# Power.net
KiCad netlist of a schematic drawn in Altium Designer
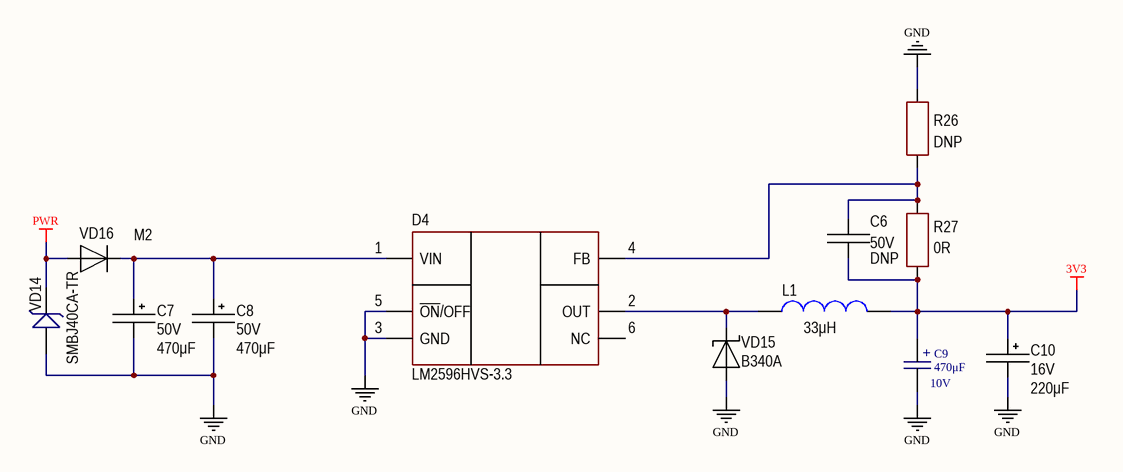
[diagram p0: Power.SchDoc]

(export (version "E")
  (design (tool "Eeschema 10.0.6"))
  (components
    (comp (ref "C6")
      (value "DNP")
      (footprint "CAP: 1206")
      (fields
        (field (name "MANUFACTURER") "Yageo")
        (field (name "PARTNUMBER") "CC1206KRX7R9BB104")
        (field (name "VALUEMANUFACTURERPARTNUMBER") "Ceramic capacitor, DNP, X7R, ±10%, 50V, 1206, -55...+125°C")
        (field (name "VOLTAGE") "50V")
      )
      (libsource (lib "capacitor") (part "Ceramic_1206"))
    )
    (comp (ref "C7")
      (value "470μF")
      (footprint "CAP: D10C5H20")
      (description "ECAP (К50-35), 470мкФ, 50В, 105°C, 20%, 10x20мм P:5мм")
      (fields
        (field (name "MANUFACTURER") "Wurth")
        (field (name "PARTNUMBER") "ECAP (К50-35)")
        (field (name "VOLTAGE") "50V")
      )
      (libsource (lib "capacitor") (part "Aluminium"))
    )
    (comp (ref "C8")
      (value "470μF")
      (footprint "CAP: D10C5H20")
      (description "ECAP (К50-35), 470мкФ, 50В, 105°C, 20%, 10x20мм P:5мм")
      (fields
        (field (name "MANUFACTURER") "Wurth")
        (field (name "PARTNUMBER") "ECAP (К50-35)")
        (field (name "VOLTAGE") "50V")
      )
      (libsource (lib "capacitor") (part "Aluminium"))
    )
    (comp (ref "C9")
      (value "470μF")
      (footprint "CAP8x10.5")
      (fields
        (field (name "VOLTAGE") "10V")
        (field (name "PARTNUMBER") "JCK1A471M080105")
        (field (name "Comment") "Capacitor_Polar")
      )
      (libsource (lib "my_library") (part "Capacitor_Polar"))
    )
    (comp (ref "C10")
      (value "220μF")
      (footprint "CAP: SMD D6.3A6.6H7.7")
      (fields
        (field (name "MANUFACTURER") "Wurth")
        (field (name "PARTNUMBER") "JCK1C221M063077")
        (field (name "VALUEMANUFACTURERPARTNUMBER") "Aluminium capacitor, 220μF, 16V, ±20%, 54mOhm, 14x10x5 mm, -55...+105°C")
        (field (name "VOLTAGE") "16V")
      )
      (libsource (lib "capacitor") (part "Aluminium"))
    )
    (comp (ref "D4")
      (value "~")
      (footprint "TO263-5L")
      (description "Buck converter")
      (fields
        (field (name "MANUFACTURER") "Texas Instruments")
        (field (name "VALUEMANUFACTURERPARTNUMBER") "DC/DC buck converter, 45V, 52MHz, 3.3V, 5A, -40...+125°C, TO263-5L")
        (field (name "PARTNUMBER") "LM2596HVS-3.3")
      )
      (libsource (lib "ic-power-supply") (part "LM2596HVS-3.3"))
    )
    (comp (ref "L1")
      (value "33μH")
      (footprint "IND: SRP7028A")
      (description "FAUL0630-330MT\r\nBMRA00060630330MA1")
      (fields (field (name "MANUFACTURER") "Bourns") (field (name "PARTNUMBER") "SRP7028A-330M"))
      (libsource (lib "inductor") (part "Inductor_SRP7028A"))
    )
    (comp (ref "R26")
      (value "DNP")
      (footprint "RES: 1206")
      (fields
        (field (name "MANUFACTURER") "Yageo")
        (field (name "PARTNUMBER") "RC1206JR-07100RL")
        (field (name "VALUEMANUFACTURERPARTNUMBER") "Resistor film, DNP, ±5%, 1206, 0.25W, -55...+125°C")
      )
      (libsource (lib "resistor") (part "Resistor_1206"))
    )
    (comp (ref "R27")
      (value "0R")
      (footprint "RES: 1206")
      (fields
        (field (name "MANUFACTURER") "Yageo")
        (field (name "PARTNUMBER") "RC1206JR-07100RL")
        (field (name "VALUEMANUFACTURERPARTNUMBER") "Resistor film, 0R, ±5%, 1206, 0.25W, -55...+125°C")
      )
      (libsource (lib "resistor") (part "Resistor_1206"))
    )
    (comp (ref "VD14")
      (value "SMBJ40CA-TR")
      (footprint "SMB")
      (fields (field (name "Comment") "suppressor"))
      (libsource (lib "my_library") (part "suppressor"))
    )
    (comp (ref "VD15")
      (value "~")
      (footprint "DIODE: SMA")
      (fields
        (field (name "VALUEMANUFACTURERPARTNUMBER") "Schottky diode, 80V, 500mA, 1V, 15pF, SMA, -55...+150°C")
        (field (name "VOLTAGE") "80V")
        (field (name "PARTNUMBER") "B340A")
      )
      (libsource (lib "diode") (part "Schottky_single"))
    )
    (comp (ref "VD16")
      (value "~")
      (footprint "DIODE: SMA")
      (fields
        (field (name "MANUFACTURER") "Micro Commercial")
        (field (name "VALUEMANUFACTURERPARTNUMBER") "Single diode, 75V, 150mA, 1V, 4ns, SOD-323, -55...+150°C")
        (field (name "VOLTAGE") "75V")
        (field (name "PARTNUMBER") "M2")
      )
      (libsource (lib "diode") (part "Diode_single"))
    )
  )
  (nets
    (net (code "1") (name "3V3") (class "Default")
      (node (ref "C10") (pin "1") (pinfunction "1_1") (pintype "passive"))
      (node (ref "C6") (pin "1") (pinfunction "1_1") (pintype "passive"))
      (node (ref "C9") (pin "1") (pinfunction "1_1") (pintype "passive"))
      (node (ref "L1") (pin "1") (pinfunction "1_1") (pintype "passive"))
      (node (ref "R27") (pin "1") (pinfunction "1_1") (pintype "passive"))
    )
    (net (code "2") (name "GND") (class "Default")
      (node (ref "C10") (pin "2") (pinfunction "2_2") (pintype "passive"))
      (node (ref "C7") (pin "2") (pinfunction "2_2") (pintype "passive"))
      (node (ref "C8") (pin "2") (pinfunction "2_2") (pintype "passive"))
      (node (ref "C9") (pin "2") (pinfunction "2_2") (pintype "passive"))
      (node (ref "D4") (pin "3") (pinfunction "GND_3") (pintype "passive"))
      (node (ref "D4") (pin "5") (pinfunction "~{ON}/OFF_5") (pintype "passive"))
      (node (ref "R26") (pin "2") (pinfunction "2_2") (pintype "passive"))
      (node (ref "VD14") (pin "2") (pinfunction "2_2") (pintype "passive"))
      (node (ref "VD15") (pin "1") (pinfunction "1_1") (pintype "passive"))
    )
    (net (code "3") (name "Net-(D4-FB)") (class "Default")
      (node (ref "C6") (pin "2") (pinfunction "2_2") (pintype "passive"))
      (node (ref "D4") (pin "4") (pinfunction "FB_4") (pintype "passive"))
      (node (ref "R26") (pin "1") (pinfunction "1_1") (pintype "passive"))
      (node (ref "R27") (pin "2") (pinfunction "2_2") (pintype "passive"))
    )
    (net (code "4") (name "Net-(D4-OUT)") (class "Default")
      (node (ref "D4") (pin "2") (pinfunction "OUT_2") (pintype "passive"))
      (node (ref "L1") (pin "2") (pinfunction "2_2") (pintype "passive"))
      (node (ref "VD15") (pin "2") (pinfunction "2_2") (pintype "passive"))
    )
    (net (code "5") (name "Net-(D4-VIN)") (class "Default")
      (node (ref "C7") (pin "1") (pinfunction "1_1") (pintype "passive"))
      (node (ref "C8") (pin "1") (pinfunction "1_1") (pintype "passive"))
      (node (ref "D4") (pin "1") (pinfunction "VIN_1") (pintype "passive"))
      (node (ref "VD16") (pin "2") (pinfunction "2_2") (pintype "passive"))
    )
    (net (code "6") (name "PWR") (class "Default")
      (node (ref "VD14") (pin "1") (pinfunction "1_1") (pintype "passive"))
      (node (ref "VD16") (pin "1") (pinfunction "1_1") (pintype "passive"))
    )
    (net (code "7") (name "unconnected-(D4-NC-Pad6)") (class "Default")
      (node (ref "D4") (pin "6") (pinfunction "NC_6") (pintype "passive"))
    )
  )
)
